# tester.net
KiCad netlist of a schematic drawn in EAGLE
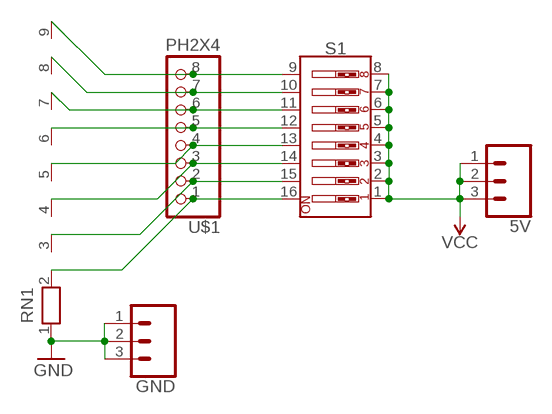
[diagram p0: schematic, sheet 1]

(export (version "E")
  (design (tool "Eeschema 10.0.6"))
  (components
    (comp (ref "5V")
      (value "CONN_03")
      (footprint "eagle-import:1X03")
      (libsource (lib "eagle-import") (part "CONN_03"))
    )
    (comp (ref "GND")
      (value "CONN_03")
      (footprint "eagle-import:1X03")
      (libsource (lib "eagle-import") (part "CONN_03"))
    )
    (comp (ref "RN1")
      (value "RN08")
      (footprint "eagle-import:RN-9")
      (libsource (lib "eagle-import") (part "RN08"))
    )
    (comp (ref "S1")
      (value "DIP-08-PTH")
      (footprint "eagle-import:DIPSWITCH-08")
      (libsource (lib "eagle-import") (part "DIP-08-PTH"))
    )
    (comp (ref "U$1")
      (value "PH2X4")
      (footprint "eagle-import:2X04")
      (libsource (lib "eagle-import") (part "PH2X4"))
    )
  )
  (nets
    (net (code "1") (name "GND") (class "Default")
      (node (ref "GND") (pin "1") (pinfunction "1_1") (pintype "passive"))
      (node (ref "GND") (pin "2") (pinfunction "2_2") (pintype "passive"))
      (node (ref "GND") (pin "3") (pinfunction "3_3") (pintype "passive"))
      (node (ref "RN1") (pin "1") (pinfunction "1_1") (pintype "passive"))
    )
    (net (code "2") (name "Net-(RN1-Pad2)") (class "Default")
      (node (ref "RN1") (pin "2") (pinfunction "2_2") (pintype "passive"))
      (node (ref "S1") (pin "16") (pinfunction "16_16") (pintype "passive"))
      (node (ref "U$1") (pin "1") (pinfunction "1_1") (pintype "passive"))
    )
    (net (code "3") (name "Net-(RN1-Pad3)") (class "Default")
      (node (ref "RN1") (pin "3") (pinfunction "3_3") (pintype "passive"))
      (node (ref "S1") (pin "15") (pinfunction "15_15") (pintype "passive"))
      (node (ref "U$1") (pin "2") (pinfunction "2_2") (pintype "passive"))
    )
    (net (code "4") (name "Net-(RN1-Pad4)") (class "Default")
      (node (ref "RN1") (pin "4") (pinfunction "4_4") (pintype "passive"))
      (node (ref "S1") (pin "14") (pinfunction "14_14") (pintype "passive"))
      (node (ref "U$1") (pin "3") (pinfunction "3_3") (pintype "passive"))
    )
    (net (code "5") (name "Net-(RN1-Pad5)") (class "Default")
      (node (ref "RN1") (pin "5") (pinfunction "5_5") (pintype "passive"))
      (node (ref "S1") (pin "13") (pinfunction "13_13") (pintype "passive"))
      (node (ref "U$1") (pin "4") (pinfunction "4_4") (pintype "passive"))
    )
    (net (code "6") (name "Net-(RN1-Pad6)") (class "Default")
      (node (ref "RN1") (pin "6") (pinfunction "6_6") (pintype "passive"))
      (node (ref "S1") (pin "12") (pinfunction "12_12") (pintype "passive"))
      (node (ref "U$1") (pin "5") (pinfunction "5_5") (pintype "passive"))
    )
    (net (code "7") (name "Net-(RN1-Pad7)") (class "Default")
      (node (ref "RN1") (pin "7") (pinfunction "7_7") (pintype "passive"))
      (node (ref "S1") (pin "11") (pinfunction "11_11") (pintype "passive"))
      (node (ref "U$1") (pin "6") (pinfunction "6_6") (pintype "passive"))
    )
    (net (code "8") (name "Net-(RN1-Pad8)") (class "Default")
      (node (ref "RN1") (pin "8") (pinfunction "8_8") (pintype "passive"))
      (node (ref "S1") (pin "10") (pinfunction "10_10") (pintype "passive"))
      (node (ref "U$1") (pin "7") (pinfunction "7_7") (pintype "passive"))
    )
    (net (code "9") (name "Net-(RN1-Pad9)") (class "Default")
      (node (ref "RN1") (pin "9") (pinfunction "9_9") (pintype "passive"))
      (node (ref "S1") (pin "9") (pinfunction "9_9") (pintype "passive"))
      (node (ref "U$1") (pin "8") (pinfunction "8_8") (pintype "passive"))
    )
    (net (code "10") (name "VCC") (class "Default")
      (node (ref "5V") (pin "1") (pinfunction "1_1") (pintype "passive"))
      (node (ref "5V") (pin "2") (pinfunction "2_2") (pintype "passive"))
      (node (ref "5V") (pin "3") (pinfunction "3_3") (pintype "passive"))
      (node (ref "S1") (pin "1") (pinfunction "1_1") (pintype "passive"))
      (node (ref "S1") (pin "2") (pinfunction "2_2") (pintype "passive"))
      (node (ref "S1") (pin "3") (pinfunction "3_3") (pintype "passive"))
      (node (ref "S1") (pin "4") (pinfunction "4_4") (pintype "passive"))
      (node (ref "S1") (pin "5") (pinfunction "5_5") (pintype "passive"))
      (node (ref "S1") (pin "6") (pinfunction "6_6") (pintype "passive"))
      (node (ref "S1") (pin "7") (pinfunction "7_7") (pintype "passive"))
      (node (ref "S1") (pin "8") (pinfunction "8_8") (pintype "passive"))
    )
  )
)
